# CM3_USBHub.net
KiCad netlist of a schematic drawn in Altium Designer
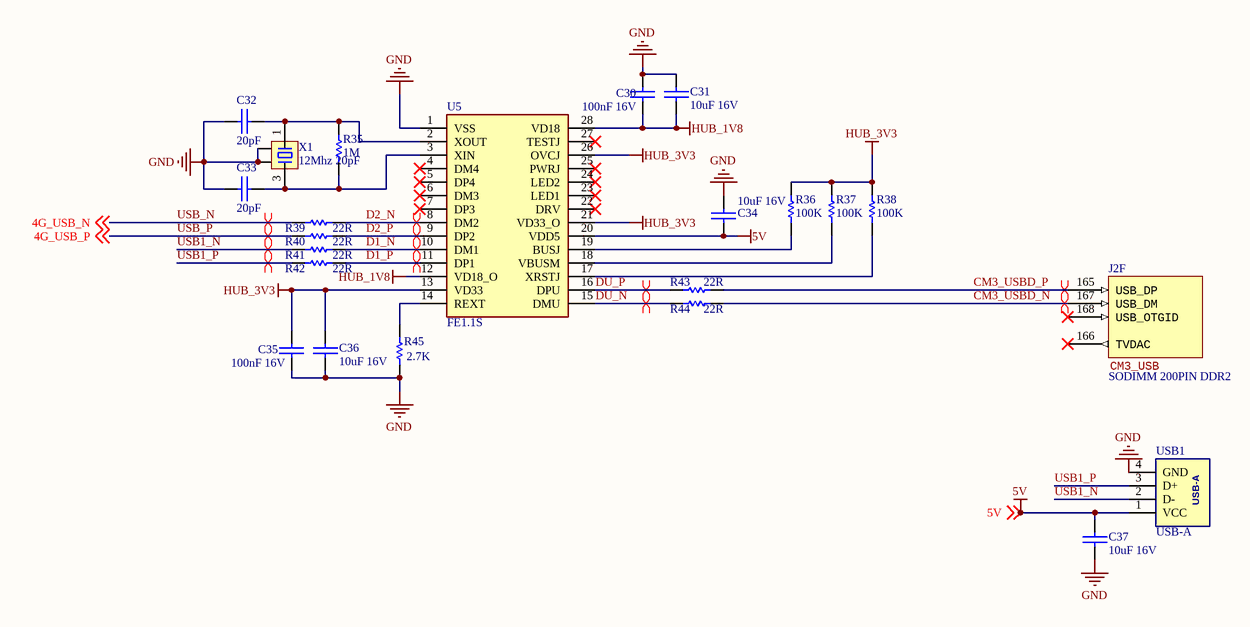
[diagram p0: CM3_USBHub.SchDoc]

(export (version "E")
  (design (tool "Eeschema 10.0.6"))
  (components
    (comp (ref "C30")
      (value "100nF 16V")
      (footprint "PCB_VPlayer:0402C")
      (description "CAP-NP")
      (libsource (lib "电容") (part "CAP-NP"))
    )
    (comp (ref "C31")
      (value "10uF 16V")
      (footprint "PCB_VPlayer:0603C")
      (description "CAP-NP")
      (libsource (lib "电容") (part "CAP-NP"))
    )
    (comp (ref "C32") (value "20pF") (footprint "PCB_VPlayer:0402C") (libsource (lib "电容") (part "CAP-NP")))
    (comp (ref "C33") (value "20pF") (footprint "PCB_VPlayer:0402C") (libsource (lib "电容") (part "CAP-NP")))
    (comp (ref "C34")
      (value "10uF 16V")
      (footprint "PCB_VPlayer:0603C")
      (description "CAP-NP")
      (libsource (lib "电容") (part "CAP-NP"))
    )
    (comp (ref "C35")
      (value "100nF 16V")
      (footprint "PCB_VPlayer:0402C")
      (description "CAP-NP")
      (libsource (lib "电容") (part "CAP-NP"))
    )
    (comp (ref "C36")
      (value "10uF 16V")
      (footprint "PCB_VPlayer:0603C")
      (description "CAP-NP")
      (libsource (lib "电容") (part "CAP-NP"))
    )
    (comp (ref "C37")
      (value "10uF 16V")
      (footprint "PCB_VPlayer:0603C")
      (libsource (lib "电容") (part "CAP-NP"))
    )
    (comp (ref "J2")
      (value "SODIMM 200PIN DDR2")
      (footprint "树莓派模块:SODIMM 200PIN - 5.2H")
      (libsource (lib "树莓派模块") (part "RPi-CM3"))
    )
    (comp (ref "R35") (value "1M") (footprint "PCB_VPlayer:0402R") (libsource (lib "电阻") (part "RES")))
    (comp (ref "R36") (value "100K") (footprint "PCB_VPlayer:0402R") (libsource (lib "电阻") (part "RES")))
    (comp (ref "R37") (value "100K") (footprint "PCB_VPlayer:0402R") (libsource (lib "电阻") (part "RES")))
    (comp (ref "R38") (value "100K") (footprint "PCB_VPlayer:0402R") (libsource (lib "电阻") (part "RES")))
    (comp (ref "R39") (value "22R") (footprint "PCB_VPlayer:0402R") (libsource (lib "电阻") (part "RES")))
    (comp (ref "R40") (value "22R") (footprint "PCB_VPlayer:0402R") (libsource (lib "电阻") (part "RES")))
    (comp (ref "R41") (value "22R") (footprint "PCB_VPlayer:0402R") (libsource (lib "电阻") (part "RES")))
    (comp (ref "R42") (value "22R") (footprint "PCB_VPlayer:0402R") (libsource (lib "电阻") (part "RES")))
    (comp (ref "R43") (value "22R") (footprint "PCB_VPlayer:0402R") (libsource (lib "电阻") (part "RES")))
    (comp (ref "R44") (value "22R") (footprint "PCB_VPlayer:0402R") (libsource (lib "电阻") (part "RES")))
    (comp (ref "R45") (value "2.7K") (footprint "PCB_VPlayer:0402R") (libsource (lib "电阻") (part "RES")))
    (comp (ref "U5")
      (value "FE1.1S")
      (footprint "SamacSys:SOP64P600X175-28N")
      (description "Integrated Circuit")
      (libsource (lib "*") (part "FE1.1S"))
    )
    (comp (ref "USB1") (value "USB-A") (footprint "USB:USB_A/F-SMT") (libsource (lib "USB") (part "USB-A")))
    (comp (ref "X1")
      (value "12Mhz 20pF")
      (footprint "OSC 3225-4P")
      (description "XTAL-4P")
      (libsource (lib "晶振") (part "XTAL-4P"))
    )
  )
  (nets
    (net (code "1") (name "/CM3_USBD_N") (class "Default")
      (node (ref "J2") (pin "167") (pinfunction "USB_DM_167") (pintype "input"))
      (node (ref "R44") (pin "1") (pinfunction "1_1") (pintype "passive"))
    )
    (net (code "2") (name "/CM3_USBD_P") (class "Default")
      (node (ref "J2") (pin "165") (pinfunction "USB_DP_165") (pintype "input"))
      (node (ref "R43") (pin "1") (pinfunction "1_1") (pintype "passive"))
    )
    (net (code "3") (name "/D1_N") (class "Default")
      (node (ref "R41") (pin "1") (pinfunction "1_1") (pintype "passive"))
      (node (ref "U5") (pin "10") (pinfunction "DM1_10") (pintype "passive"))
    )
    (net (code "4") (name "/D1_P") (class "Default")
      (node (ref "R42") (pin "1") (pinfunction "1_1") (pintype "passive"))
      (node (ref "U5") (pin "11") (pinfunction "DP1_11") (pintype "passive"))
    )
    (net (code "5") (name "/D2_N") (class "Default")
      (node (ref "R39") (pin "1") (pinfunction "1_1") (pintype "passive"))
      (node (ref "U5") (pin "8") (pinfunction "DM2_8") (pintype "passive"))
    )
    (net (code "6") (name "/D2_P") (class "Default")
      (node (ref "R40") (pin "1") (pinfunction "1_1") (pintype "passive"))
      (node (ref "U5") (pin "9") (pinfunction "DP2_9") (pintype "passive"))
    )
    (net (code "7") (name "/DU_N") (class "Default")
      (node (ref "R44") (pin "2") (pinfunction "2_2") (pintype "passive"))
      (node (ref "U5") (pin "15") (pinfunction "DMU_15") (pintype "passive"))
    )
    (net (code "8") (name "/DU_P") (class "Default")
      (node (ref "R43") (pin "2") (pinfunction "2_2") (pintype "passive"))
      (node (ref "U5") (pin "16") (pinfunction "DPU_16") (pintype "passive"))
    )
    (net (code "9") (name "/USB1_N") (class "Default")
      (node (ref "R41") (pin "2") (pinfunction "2_2") (pintype "passive"))
      (node (ref "USB1") (pin "2") (pinfunction "D-_2") (pintype "passive"))
    )
    (net (code "10") (name "/USB1_P") (class "Default")
      (node (ref "R42") (pin "2") (pinfunction "2_2") (pintype "passive"))
      (node (ref "USB1") (pin "3") (pinfunction "D+_3") (pintype "passive"))
    )
    (net (code "11") (name "4G_USB_N") (class "Default")
      (node (ref "R39") (pin "2") (pinfunction "2_2") (pintype "passive"))
    )
    (net (code "12") (name "4G_USB_P") (class "Default")
      (node (ref "R40") (pin "2") (pinfunction "2_2") (pintype "passive"))
    )
    (net (code "13") (name "5V") (class "Default")
      (node (ref "C34") (pin "2") (pinfunction "2_2") (pintype "passive"))
      (node (ref "C37") (pin "2") (pinfunction "2_2") (pintype "passive"))
      (node (ref "U5") (pin "20") (pinfunction "VDD5_20") (pintype "passive"))
      (node (ref "USB1") (pin "1") (pinfunction "VCC_1") (pintype "passive"))
    )
    (net (code "14") (name "GND") (class "Default")
      (node (ref "C30") (pin "2") (pinfunction "2_2") (pintype "passive"))
      (node (ref "C31") (pin "1") (pinfunction "1_1") (pintype "passive"))
      (node (ref "C32") (pin "2") (pinfunction "2_2") (pintype "passive"))
      (node (ref "C33") (pin "1") (pinfunction "1_1") (pintype "passive"))
      (node (ref "C34") (pin "1") (pinfunction "1_1") (pintype "passive"))
      (node (ref "C35") (pin "1") (pinfunction "1_1") (pintype "passive"))
      (node (ref "C36") (pin "2") (pinfunction "2_2") (pintype "passive"))
      (node (ref "C37") (pin "1") (pinfunction "1_1") (pintype "passive"))
      (node (ref "R45") (pin "1") (pinfunction "1_1") (pintype "passive"))
      (node (ref "U5") (pin "1") (pinfunction "VSS_1") (pintype "passive"))
      (node (ref "USB1") (pin "4") (pinfunction "GND_4") (pintype "passive"))
      (node (ref "X1") (pin "2") (pinfunction "2_2") (pintype "passive"))
      (node (ref "X1") (pin "4") (pinfunction "4_4") (pintype "passive"))
    )
    (net (code "15") (name "HUB_1V8") (class "Default")
      (node (ref "C30") (pin "1") (pinfunction "1_1") (pintype "passive"))
      (node (ref "C31") (pin "2") (pinfunction "2_2") (pintype "passive"))
      (node (ref "U5") (pin "12") (pinfunction "VD18_O_12") (pintype "passive"))
      (node (ref "U5") (pin "28") (pinfunction "VD18_28") (pintype "passive"))
    )
    (net (code "16") (name "HUB_3V3") (class "Default")
      (node (ref "C35") (pin "2") (pinfunction "2_2") (pintype "passive"))
      (node (ref "C36") (pin "1") (pinfunction "1_1") (pintype "passive"))
      (node (ref "R36") (pin "2") (pinfunction "2_2") (pintype "passive"))
      (node (ref "R37") (pin "2") (pinfunction "2_2") (pintype "passive"))
      (node (ref "R38") (pin "2") (pinfunction "2_2") (pintype "passive"))
      (node (ref "U5") (pin "13") (pinfunction "VD33_13") (pintype "passive"))
      (node (ref "U5") (pin "21") (pinfunction "VD33_O_21") (pintype "passive"))
      (node (ref "U5") (pin "26") (pinfunction "OVCJ_26") (pintype "passive"))
    )
    (net (code "17") (name "Net-(U5-BUSJ)") (class "Default")
      (node (ref "R36") (pin "1") (pinfunction "1_1") (pintype "passive"))
      (node (ref "U5") (pin "19") (pinfunction "BUSJ_19") (pintype "passive"))
    )
    (net (code "18") (name "Net-(U5-REXT)") (class "Default")
      (node (ref "R45") (pin "2") (pinfunction "2_2") (pintype "passive"))
      (node (ref "U5") (pin "14") (pinfunction "REXT_14") (pintype "passive"))
    )
    (net (code "19") (name "Net-(U5-VBUSM)") (class "Default")
      (node (ref "R37") (pin "1") (pinfunction "1_1") (pintype "passive"))
      (node (ref "U5") (pin "18") (pinfunction "VBUSM_18") (pintype "passive"))
    )
    (net (code "20") (name "Net-(U5-XIN)") (class "Default")
      (node (ref "C33") (pin "2") (pinfunction "2_2") (pintype "passive"))
      (node (ref "R35") (pin "1") (pinfunction "1_1") (pintype "passive"))
      (node (ref "U5") (pin "3") (pinfunction "XIN_3") (pintype "passive"))
      (node (ref "X1") (pin "3") (pinfunction "3_3") (pintype "passive"))
    )
    (net (code "21") (name "Net-(U5-XOUT)") (class "Default")
      (node (ref "C32") (pin "1") (pinfunction "1_1") (pintype "passive"))
      (node (ref "R35") (pin "2") (pinfunction "2_2") (pintype "passive"))
      (node (ref "U5") (pin "2") (pinfunction "XOUT_2") (pintype "passive"))
      (node (ref "X1") (pin "1") (pinfunction "1_1") (pintype "passive"))
    )
    (net (code "22") (name "Net-(U5-XRSTJ)") (class "Default")
      (node (ref "R38") (pin "1") (pinfunction "1_1") (pintype "passive"))
      (node (ref "U5") (pin "17") (pinfunction "XRSTJ_17") (pintype "passive"))
    )
    (net (code "23") (name "unconnected-(J2F-TVDAC-Pad166)") (class "Default")
      (node (ref "J2") (pin "166") (pinfunction "TVDAC_166") (pintype "output+no_connect"))
    )
    (net (code "24") (name "unconnected-(J2F-USB_OTGID-Pad168)") (class "Default")
      (node (ref "J2") (pin "168") (pinfunction "USB_OTGID_168") (pintype "input+no_connect"))
    )
    (net (code "25") (name "unconnected-(U5-DM3-Pad6)") (class "Default")
      (node (ref "U5") (pin "6") (pinfunction "DM3_6") (pintype "passive+no_connect"))
    )
    (net (code "26") (name "unconnected-(U5-DM4-Pad4)") (class "Default")
      (node (ref "U5") (pin "4") (pinfunction "DM4_4") (pintype "passive+no_connect"))
    )
    (net (code "27") (name "unconnected-(U5-DP3-Pad7)") (class "Default")
      (node (ref "U5") (pin "7") (pinfunction "DP3_7") (pintype "passive+no_connect"))
    )
    (net (code "28") (name "unconnected-(U5-DP4-Pad5)") (class "Default")
      (node (ref "U5") (pin "5") (pinfunction "DP4_5") (pintype "passive+no_connect"))
    )
    (net (code "29") (name "unconnected-(U5-DRV-Pad22)") (class "Default")
      (node (ref "U5") (pin "22") (pinfunction "DRV_22") (pintype "passive+no_connect"))
    )
    (net (code "30") (name "unconnected-(U5-LED1-Pad23)") (class "Default")
      (node (ref "U5") (pin "23") (pinfunction "LED1_23") (pintype "passive+no_connect"))
    )
    (net (code "31") (name "unconnected-(U5-LED2-Pad24)") (class "Default")
      (node (ref "U5") (pin "24") (pinfunction "LED2_24") (pintype "passive+no_connect"))
    )
    (net (code "32") (name "unconnected-(U5-PWRJ-Pad25)") (class "Default")
      (node (ref "U5") (pin "25") (pinfunction "PWRJ_25") (pintype "passive+no_connect"))
    )
    (net (code "33") (name "unconnected-(U5-TESTJ-Pad27)") (class "Default")
      (node (ref "U5") (pin "27") (pinfunction "TESTJ_27") (pintype "passive+no_connect"))
    )
  )
)
